# partybooth.net
KiCad netlist of a schematic drawn in EAGLE
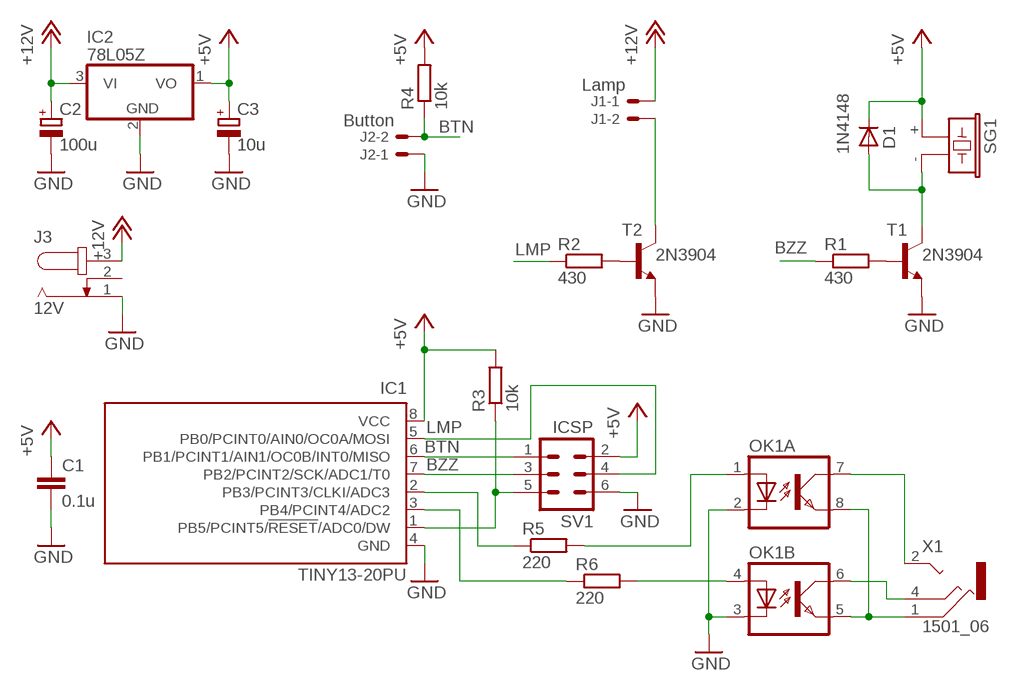
[diagram p0: schematic, sheet 1]

(export (version "E")
  (design (tool "Eeschema 10.0.6"))
  (components
    (comp (ref "C1")
      (value "0.1u")
      (footprint "eagle-import:C025_050-025X075")
      (libsource (lib "eagle-import") (part "C-EU025_050-025X075"))
    )
    (comp (ref "C2")
      (value "100u")
      (footprint "eagle-import:B45181B")
      (libsource (lib "eagle-import") (part "CPOL-EUB45181B"))
    )
    (comp (ref "C3")
      (value "10u")
      (footprint "eagle-import:B45181B")
      (libsource (lib "eagle-import") (part "CPOL-EUB45181B"))
    )
    (comp (ref "D1")
      (value "1N4148")
      (footprint "eagle-import:DO35-7")
      (libsource (lib "eagle-import") (part "1N4148DO35-7"))
    )
    (comp (ref "IC1")
      (value "TINY13-20PU")
      (footprint "eagle-import:DIL08")
      (fields (field (name "MPN") "ATTINY13-20PU"))
      (libsource (lib "eagle-import") (part "TINY13PU-20"))
    )
    (comp (ref "IC2")
      (value "78L05Z")
      (footprint "eagle-import:TO92")
      (libsource (lib "eagle-import") (part "78ZL05"))
    )
    (comp (ref "J1")
      (value "Lamp")
      (footprint "eagle-import:6410-02")
      (libsource (lib "eagle-import") (part "22-?-0227-2021"))
    )
    (comp (ref "J2")
      (value "Button")
      (footprint "eagle-import:6410-02")
      (libsource (lib "eagle-import") (part "22-?-0227-2021"))
    )
    (comp (ref "J3")
      (value "12V")
      (footprint "eagle-import:SPC4077")
      (libsource (lib "eagle-import") (part "JACK-PLUG0"))
    )
    (comp (ref "OK1")
      (value "ILD2")
      (footprint "eagle-import:DIL08")
      (libsource (lib "eagle-import") (part "ILD2"))
    )
    (comp (ref "R1")
      (value "430")
      (footprint "eagle-import:0204_7")
      (libsource (lib "eagle-import") (part "R-EU_0204/7"))
    )
    (comp (ref "R2")
      (value "430")
      (footprint "eagle-import:0204_7")
      (libsource (lib "eagle-import") (part "R-EU_0204/7"))
    )
    (comp (ref "R3")
      (value "10k")
      (footprint "eagle-import:0204_7")
      (libsource (lib "eagle-import") (part "R-EU_0204/7"))
    )
    (comp (ref "R4")
      (value "10k")
      (footprint "eagle-import:0204_7")
      (libsource (lib "eagle-import") (part "R-EU_0204/7"))
    )
    (comp (ref "R5")
      (value "220")
      (footprint "eagle-import:0204_7")
      (libsource (lib "eagle-import") (part "R-EU_0204/7"))
    )
    (comp (ref "R6")
      (value "220")
      (footprint "eagle-import:0204_7")
      (libsource (lib "eagle-import") (part "R-EU_0204/7"))
    )
    (comp (ref "SG1")
      (value "F/CM12P")
      (footprint "eagle-import:F_CM12P")
      (libsource (lib "eagle-import") (part "F/CM12P"))
    )
    (comp (ref "SV1")
      (value "ICSP")
      (footprint "eagle-import:MA03-2")
      (libsource (lib "eagle-import") (part "MA03-2"))
    )
    (comp (ref "T1")
      (value "2N3904")
      (footprint "eagle-import:TO92")
      (libsource (lib "eagle-import") (part "2N3904"))
    )
    (comp (ref "T2")
      (value "2N3904")
      (footprint "eagle-import:TO92")
      (libsource (lib "eagle-import") (part "2N3904"))
    )
    (comp (ref "X1")
      (value "1501_06")
      (footprint "eagle-import:1501_06")
      (libsource (lib "eagle-import") (part "1501_06"))
    )
  )
  (nets
    (net (code "1") (name "+5V") (class "Default")
      (node (ref "C1") (pin "1") (pinfunction "1_1") (pintype "passive"))
      (node (ref "C3") (pin "+") (pinfunction "+_+") (pintype "passive"))
      (node (ref "D1") (pin "C") (pinfunction "C_C") (pintype "passive"))
      (node (ref "IC1") (pin "8") (pinfunction "VCC_8") (pintype "power_in"))
      (node (ref "IC2") (pin "1") (pinfunction "VO_1") (pintype "passive"))
      (node (ref "R3") (pin "2") (pinfunction "2_2") (pintype "passive"))
      (node (ref "R4") (pin "2") (pinfunction "2_2") (pintype "passive"))
      (node (ref "SG1") (pin "+") (pinfunction "1_+") (pintype "passive"))
      (node (ref "SV1") (pin "2") (pinfunction "2_2") (pintype "passive"))
    )
    (net (code "2") (name "+12V") (class "Default")
      (node (ref "C2") (pin "+") (pinfunction "+_+") (pintype "passive"))
      (node (ref "IC2") (pin "3") (pinfunction "VI_3") (pintype "input"))
      (node (ref "J1") (pin "1") (pinfunction "S_1") (pintype "passive"))
      (node (ref "J3") (pin "3") (pinfunction "3_3") (pintype "passive"))
    )
    (net (code "3") (name "/BTN") (class "Default")
      (node (ref "IC1") (pin "6") (pinfunction "PB1/PCINT1/AIN1/OC0B/INT0/MISO_6") (pintype "bidirectional"))
      (node (ref "J2") (pin "2") (pinfunction "S_2") (pintype "passive"))
      (node (ref "R4") (pin "1") (pinfunction "1_1") (pintype "passive"))
      (node (ref "SV1") (pin "1") (pinfunction "1_1") (pintype "passive"))
    )
    (net (code "4") (name "/BZZ") (class "Default")
      (node (ref "IC1") (pin "7") (pinfunction "PB2/PCINT2/SCK/ADC1/T0_7") (pintype "bidirectional"))
      (node (ref "R1") (pin "1") (pinfunction "1_1") (pintype "passive"))
      (node (ref "SV1") (pin "3") (pinfunction "3_3") (pintype "passive"))
    )
    (net (code "5") (name "/LMP") (class "Default")
      (node (ref "IC1") (pin "5") (pinfunction "PB0/PCINT0/AIN0/OC0A/MOSI_5") (pintype "bidirectional"))
      (node (ref "R2") (pin "1") (pinfunction "1_1") (pintype "passive"))
      (node (ref "SV1") (pin "4") (pinfunction "4_4") (pintype "passive"))
    )
    (net (code "6") (name "GND") (class "Default")
      (node (ref "C1") (pin "2") (pinfunction "2_2") (pintype "passive"))
      (node (ref "C2") (pin "-") (pinfunction "-_-") (pintype "passive"))
      (node (ref "C3") (pin "-") (pinfunction "-_-") (pintype "passive"))
      (node (ref "IC1") (pin "4") (pinfunction "GND_4") (pintype "power_in"))
      (node (ref "IC2") (pin "2") (pinfunction "GND_2") (pintype "passive"))
      (node (ref "J2") (pin "1") (pinfunction "S_1") (pintype "passive"))
      (node (ref "J3") (pin "1") (pinfunction "1_1") (pintype "passive"))
      (node (ref "OK1") (pin "2") (pinfunction "C_2") (pintype "passive"))
      (node (ref "OK1") (pin "3") (pinfunction "C_3") (pintype "passive"))
      (node (ref "SV1") (pin "6") (pinfunction "6_6") (pintype "passive"))
      (node (ref "T1") (pin "3") (pinfunction "E_3") (pintype "passive"))
      (node (ref "T2") (pin "3") (pinfunction "E_3") (pintype "passive"))
    )
    (net (code "7") (name "Net-(IC1-PB3{slash}PCINT3{slash}CLKI{slash}ADC3)") (class "Default")
      (node (ref "IC1") (pin "2") (pinfunction "PB3/PCINT3/CLKI/ADC3_2") (pintype "bidirectional"))
      (node (ref "R5") (pin "1") (pinfunction "1_1") (pintype "passive"))
    )
    (net (code "8") (name "Net-(IC1-PB4{slash}PCINT4{slash}ADC2)") (class "Default")
      (node (ref "IC1") (pin "3") (pinfunction "PB4/PCINT4/ADC2_3") (pintype "bidirectional"))
      (node (ref "R6") (pin "1") (pinfunction "1_1") (pintype "passive"))
    )
    (net (code "9") (name "Net-(IC1-PB5{slash}PCINT5{slash}~{RESET}{slash}ADC0{slash}DW)") (class "Default")
      (node (ref "IC1") (pin "1") (pinfunction "PB5/PCINT5/~{RESET}/ADC0/DW_1") (pintype "bidirectional"))
      (node (ref "R3") (pin "1") (pinfunction "1_1") (pintype "passive"))
      (node (ref "SV1") (pin "5") (pinfunction "5_5") (pintype "passive"))
    )
    (net (code "10") (name "Net-(J1B-S)") (class "Default")
      (node (ref "J1") (pin "2") (pinfunction "S_2") (pintype "passive"))
      (node (ref "T2") (pin "1") (pinfunction "C_1") (pintype "passive"))
    )
    (net (code "11") (name "Net-(OK1A-A)") (class "Default")
      (node (ref "OK1") (pin "1") (pinfunction "A_1") (pintype "passive"))
      (node (ref "R5") (pin "2") (pinfunction "2_2") (pintype "passive"))
    )
    (net (code "12") (name "Net-(OK1A-COL)") (class "Default")
      (node (ref "OK1") (pin "7") (pinfunction "COL_7") (pintype "passive"))
      (node (ref "X1") (pin "2") (pinfunction "2_2") (pintype "passive"))
    )
    (net (code "13") (name "Net-(OK1A-EMIT)") (class "Default")
      (node (ref "OK1") (pin "5") (pinfunction "EMIT_5") (pintype "passive"))
      (node (ref "OK1") (pin "8") (pinfunction "EMIT_8") (pintype "passive"))
      (node (ref "X1") (pin "1") (pinfunction "1_1") (pintype "passive"))
    )
    (net (code "14") (name "Net-(OK1B-A)") (class "Default")
      (node (ref "OK1") (pin "4") (pinfunction "A_4") (pintype "passive"))
      (node (ref "R6") (pin "2") (pinfunction "2_2") (pintype "passive"))
    )
    (net (code "15") (name "Net-(OK1B-COL)") (class "Default")
      (node (ref "OK1") (pin "6") (pinfunction "COL_6") (pintype "passive"))
      (node (ref "X1") (pin "4") (pinfunction "3_4") (pintype "passive"))
    )
    (net (code "16") (name "Net-(SG1-2)") (class "Default")
      (node (ref "D1") (pin "A") (pinfunction "A_A") (pintype "passive"))
      (node (ref "SG1") (pin "-") (pinfunction "2_-") (pintype "passive"))
      (node (ref "T1") (pin "1") (pinfunction "C_1") (pintype "passive"))
    )
    (net (code "17") (name "Net-(T1-B)") (class "Default")
      (node (ref "R1") (pin "2") (pinfunction "2_2") (pintype "passive"))
      (node (ref "T1") (pin "2") (pinfunction "B_2") (pintype "passive"))
    )
    (net (code "18") (name "Net-(T2-B)") (class "Default")
      (node (ref "R2") (pin "2") (pinfunction "2_2") (pintype "passive"))
      (node (ref "T2") (pin "2") (pinfunction "B_2") (pintype "passive"))
    )
    (net (code "19") (name "unconnected-(J3-Pad2)") (class "Default")
      (node (ref "J3") (pin "2") (pinfunction "2_2") (pintype "passive"))
    )
  )
)
